# GD_Tcontroller_485.net
KiCad netlist of a schematic drawn in Altium Designer
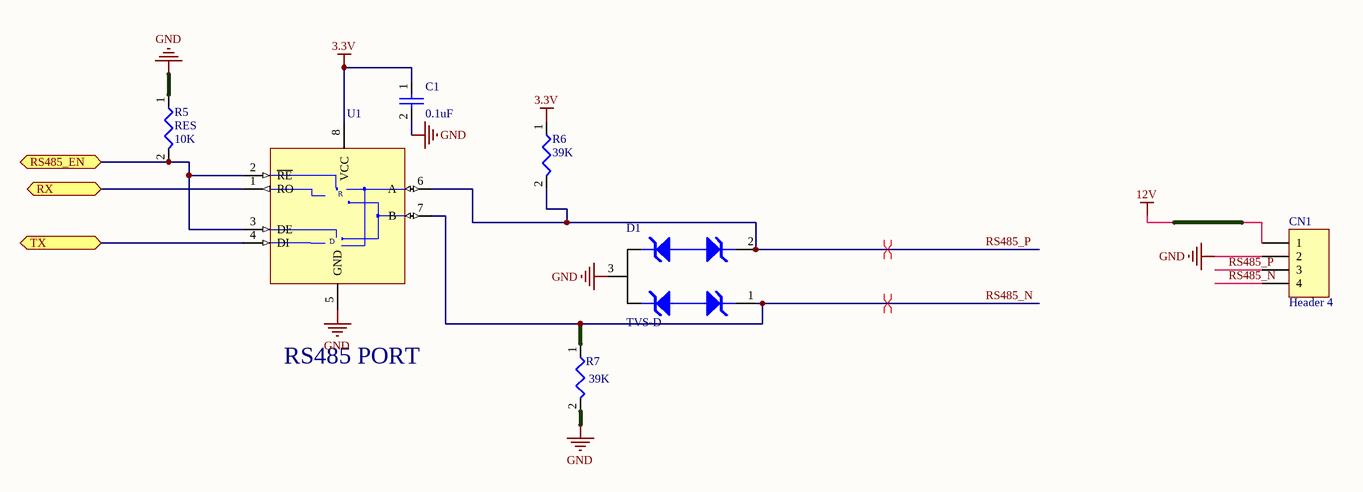
[diagram p0: GD_Tcontroller_485.SchDoc]

(export (version "E")
  (design (tool "Eeschema 10.0.6"))
  (components
    (comp (ref "C1")
      (value "0.1uF")
      (footprint "C0805")
      (description "CAP SMD CR X7R 50V 10% 0.1uF 0805 ROHS")
      (fields (field (name "MANUFACTURER") "YAGEO") (field (name "Comment") "CAP"))
      (libsource (lib "enlogic") (part "CAP"))
    )
    (comp (ref "CN1")
      (value "Header 4")
      (footprint "HT5.08-4P-H")
      (description "Header, 4-Pin")
      (libsource (lib "Enlogic_CN") (part "Header 4"))
    )
    (comp (ref "D1")
      (value "TVS-D")
      (footprint "SOT23-123")
      (description "DIODE TVS 7V 12V 17A 400W SOT-23 SMD ROHS")
      (fields (field (name "MANUFACTURER") "BOURNS"))
      (libsource (lib "enlogic") (part "TVS-D"))
    )
    (comp (ref "R5")
      (value "RES")
      (footprint "R0805")
      (description "RES THICK_FILM SMD 10K ohm 5% 1/10W ROHS 0603")
      (fields (field (name "MANUFACTURER") "YAGEO") (field (name "ALTIUM_VALUE") "10K"))
      (libsource (lib "Enlogic") (part "RES"))
    )
    (comp (ref "R6")
      (value "39K")
      (footprint "R0805")
      (description "RES THICK_FILM SMD 39K 5% 1/8W ROHS 0805")
      (fields (field (name "MANUFACTURER") "YAGEO") (field (name "Comment") "RES"))
      (libsource (lib "enlogic") (part "RES"))
    )
    (comp (ref "R7")
      (value "39K")
      (footprint "R0805")
      (description "RES THICK_FILM SMD 39K 5% 1/8W ROHS 0805")
      (fields (field (name "MANUFACTURER") "YAGEO") (field (name "Comment") "RES"))
      (libsource (lib "enlogic") (part "RES"))
    )
    (comp (ref "U1")
      (value "SN65HVD08D")
      (footprint "SOIC8")
      (description "IC 5V,RS-485,10Mbps,16KV,TRANSCEIVERS,SOIC-8,ROHS")
      (fields (field (name "MANUFACTURER") "Texas Instruments"))
      (libsource (lib "enlogic") (part "SN65HVD11D"))
    )
  )
  (nets
    (net (code "1") (name "/RS485_EN") (class "Default")
      (node (ref "R5") (pin "2") (pinfunction "2_2") (pintype "passive"))
      (node (ref "U1") (pin "2") (pinfunction "~{RE}_2") (pintype "input"))
      (node (ref "U1") (pin "3") (pinfunction "DE_3") (pintype "input"))
    )
    (net (code "2") (name "/RS485_N") (class "Default")
      (node (ref "CN1") (pin "4") (pinfunction "4_4") (pintype "passive"))
      (node (ref "D1") (pin "1") (pinfunction "1_1") (pintype "passive"))
      (node (ref "R7") (pin "1") (pinfunction "1_1") (pintype "passive"))
      (node (ref "U1") (pin "7") (pinfunction "B_7") (pintype "bidirectional"))
    )
    (net (code "3") (name "/RS485_P") (class "Default")
      (node (ref "CN1") (pin "3") (pinfunction "3_3") (pintype "passive"))
      (node (ref "D1") (pin "2") (pinfunction "2_2") (pintype "passive"))
      (node (ref "R6") (pin "2") (pinfunction "2_2") (pintype "passive"))
      (node (ref "U1") (pin "6") (pinfunction "A_6") (pintype "bidirectional"))
    )
    (net (code "4") (name "/RX") (class "Default")
      (node (ref "U1") (pin "1") (pinfunction "RO_1") (pintype "output"))
    )
    (net (code "5") (name "/TX") (class "Default")
      (node (ref "U1") (pin "4") (pinfunction "DI_4") (pintype "input"))
    )
    (net (code "6") (name "3.3V") (class "Default")
      (node (ref "C1") (pin "1") (pinfunction "1_1") (pintype "passive"))
      (node (ref "R6") (pin "1") (pinfunction "1_1") (pintype "passive"))
      (node (ref "U1") (pin "8") (pinfunction "VCC_8") (pintype "power_in"))
    )
    (net (code "7") (name "12V") (class "Default")
      (node (ref "CN1") (pin "1") (pinfunction "1_1") (pintype "passive"))
    )
    (net (code "8") (name "GND") (class "Default")
      (node (ref "C1") (pin "2") (pinfunction "2_2") (pintype "passive"))
      (node (ref "CN1") (pin "2") (pinfunction "2_2") (pintype "passive"))
      (node (ref "D1") (pin "3") (pinfunction "3_3") (pintype "passive"))
      (node (ref "R5") (pin "1") (pinfunction "1_1") (pintype "passive"))
      (node (ref "R7") (pin "2") (pinfunction "2_2") (pintype "passive"))
      (node (ref "U1") (pin "5") (pinfunction "GND_5") (pintype "power_in"))
    )
  )
)
